# wavemeter_v1.net
KiCad netlist of a schematic drawn in EAGLE
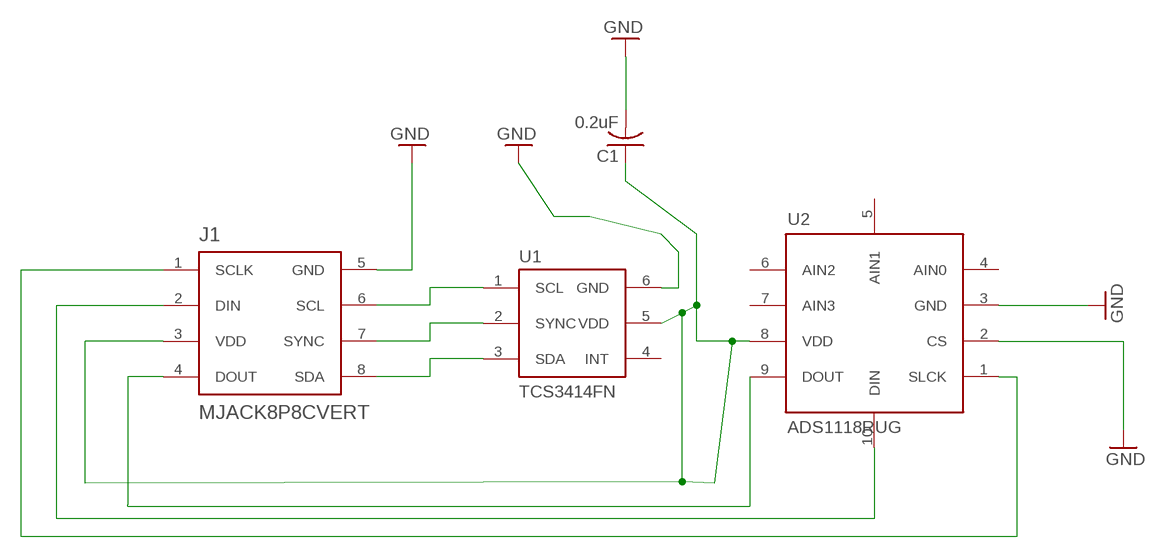
[diagram p0: schematic, sheet 1]

(export (version "E")
  (design (tool "Eeschema 10.0.6"))
  (components
    (comp (ref "C1")
      (value "0.2uF")
      (footprint "eagle-import:C0603")
      (libsource (lib "eagle-import") (part "C-USC0603"))
    )
    (comp (ref "J1")
      (value "MJACK8P8CVERT")
      (footprint "eagle-import:MJACK8P8C")
      (libsource (lib "eagle-import") (part "MJACK8P8CVERT"))
    )
    (comp (ref "U1")
      (value "TCS3414FN")
      (footprint "eagle-import:TCS3414")
      (libsource (lib "eagle-import") (part "TCS3414FN"))
    )
    (comp (ref "U2")
      (value "ADS1118RUG")
      (footprint "eagle-import:ADS1118")
      (libsource (lib "eagle-import") (part "ADS1118RUG"))
    )
  )
  (nets
    (net (code "1") (name "GND") (class "Default")
      (node (ref "C1") (pin "2") (pinfunction "2_2") (pintype "passive"))
      (node (ref "J1") (pin "5") (pinfunction "GND_5") (pintype "bidirectional"))
      (node (ref "U1") (pin "6") (pinfunction "GND_6") (pintype "bidirectional"))
      (node (ref "U2") (pin "2") (pinfunction "CS_2") (pintype "bidirectional"))
      (node (ref "U2") (pin "3") (pinfunction "GND_3") (pintype "bidirectional"))
    )
    (net (code "2") (name "Net-(J1-DIN)") (class "Default")
      (node (ref "J1") (pin "2") (pinfunction "DIN_2") (pintype "bidirectional"))
      (node (ref "U2") (pin "10") (pinfunction "DIN_10") (pintype "bidirectional"))
    )
    (net (code "3") (name "Net-(J1-DOUT)") (class "Default")
      (node (ref "J1") (pin "4") (pinfunction "DOUT_4") (pintype "bidirectional"))
      (node (ref "U2") (pin "9") (pinfunction "DOUT_9") (pintype "bidirectional"))
    )
    (net (code "4") (name "Net-(J1-SCL)") (class "Default")
      (node (ref "J1") (pin "6") (pinfunction "SCL_6") (pintype "bidirectional"))
      (node (ref "U1") (pin "1") (pinfunction "SCL_1") (pintype "bidirectional"))
    )
    (net (code "5") (name "Net-(J1-SCLK)") (class "Default")
      (node (ref "J1") (pin "1") (pinfunction "SCLK_1") (pintype "bidirectional"))
      (node (ref "U2") (pin "1") (pinfunction "SLCK_1") (pintype "bidirectional"))
    )
    (net (code "6") (name "Net-(J1-SDA)") (class "Default")
      (node (ref "J1") (pin "8") (pinfunction "SDA_8") (pintype "bidirectional"))
      (node (ref "U1") (pin "3") (pinfunction "SDA_3") (pintype "bidirectional"))
    )
    (net (code "7") (name "Net-(J1-SYNC)") (class "Default")
      (node (ref "J1") (pin "7") (pinfunction "SYNC_7") (pintype "bidirectional"))
      (node (ref "U1") (pin "2") (pinfunction "SYNC_2") (pintype "bidirectional"))
    )
    (net (code "8") (name "Net-(J1-VDD)") (class "Default")
      (node (ref "C1") (pin "1") (pinfunction "1_1") (pintype "passive"))
      (node (ref "J1") (pin "3") (pinfunction "VDD_3") (pintype "bidirectional"))
      (node (ref "U1") (pin "5") (pinfunction "VDD_5") (pintype "bidirectional"))
      (node (ref "U2") (pin "8") (pinfunction "VDD_8") (pintype "bidirectional"))
    )
    (net (code "9") (name "unconnected-(U1-INT-Pad4)") (class "Default")
      (node (ref "U1") (pin "4") (pinfunction "INT_4") (pintype "bidirectional"))
    )
    (net (code "10") (name "unconnected-(U2-AIN0-Pad4)") (class "Default")
      (node (ref "U2") (pin "4") (pinfunction "AIN0_4") (pintype "bidirectional"))
    )
    (net (code "11") (name "unconnected-(U2-AIN1-Pad5)") (class "Default")
      (node (ref "U2") (pin "5") (pinfunction "AIN1_5") (pintype "bidirectional"))
    )
    (net (code "12") (name "unconnected-(U2-AIN2-Pad6)") (class "Default")
      (node (ref "U2") (pin "6") (pinfunction "AIN2_6") (pintype "bidirectional"))
    )
    (net (code "13") (name "unconnected-(U2-AIN3-Pad7)") (class "Default")
      (node (ref "U2") (pin "7") (pinfunction "AIN3_7") (pintype "bidirectional"))
    )
  )
)
